# Adafruit_Mini_PiTFT_-_135x240_Color_TFT.net
KiCad netlist of a schematic drawn in EAGLE
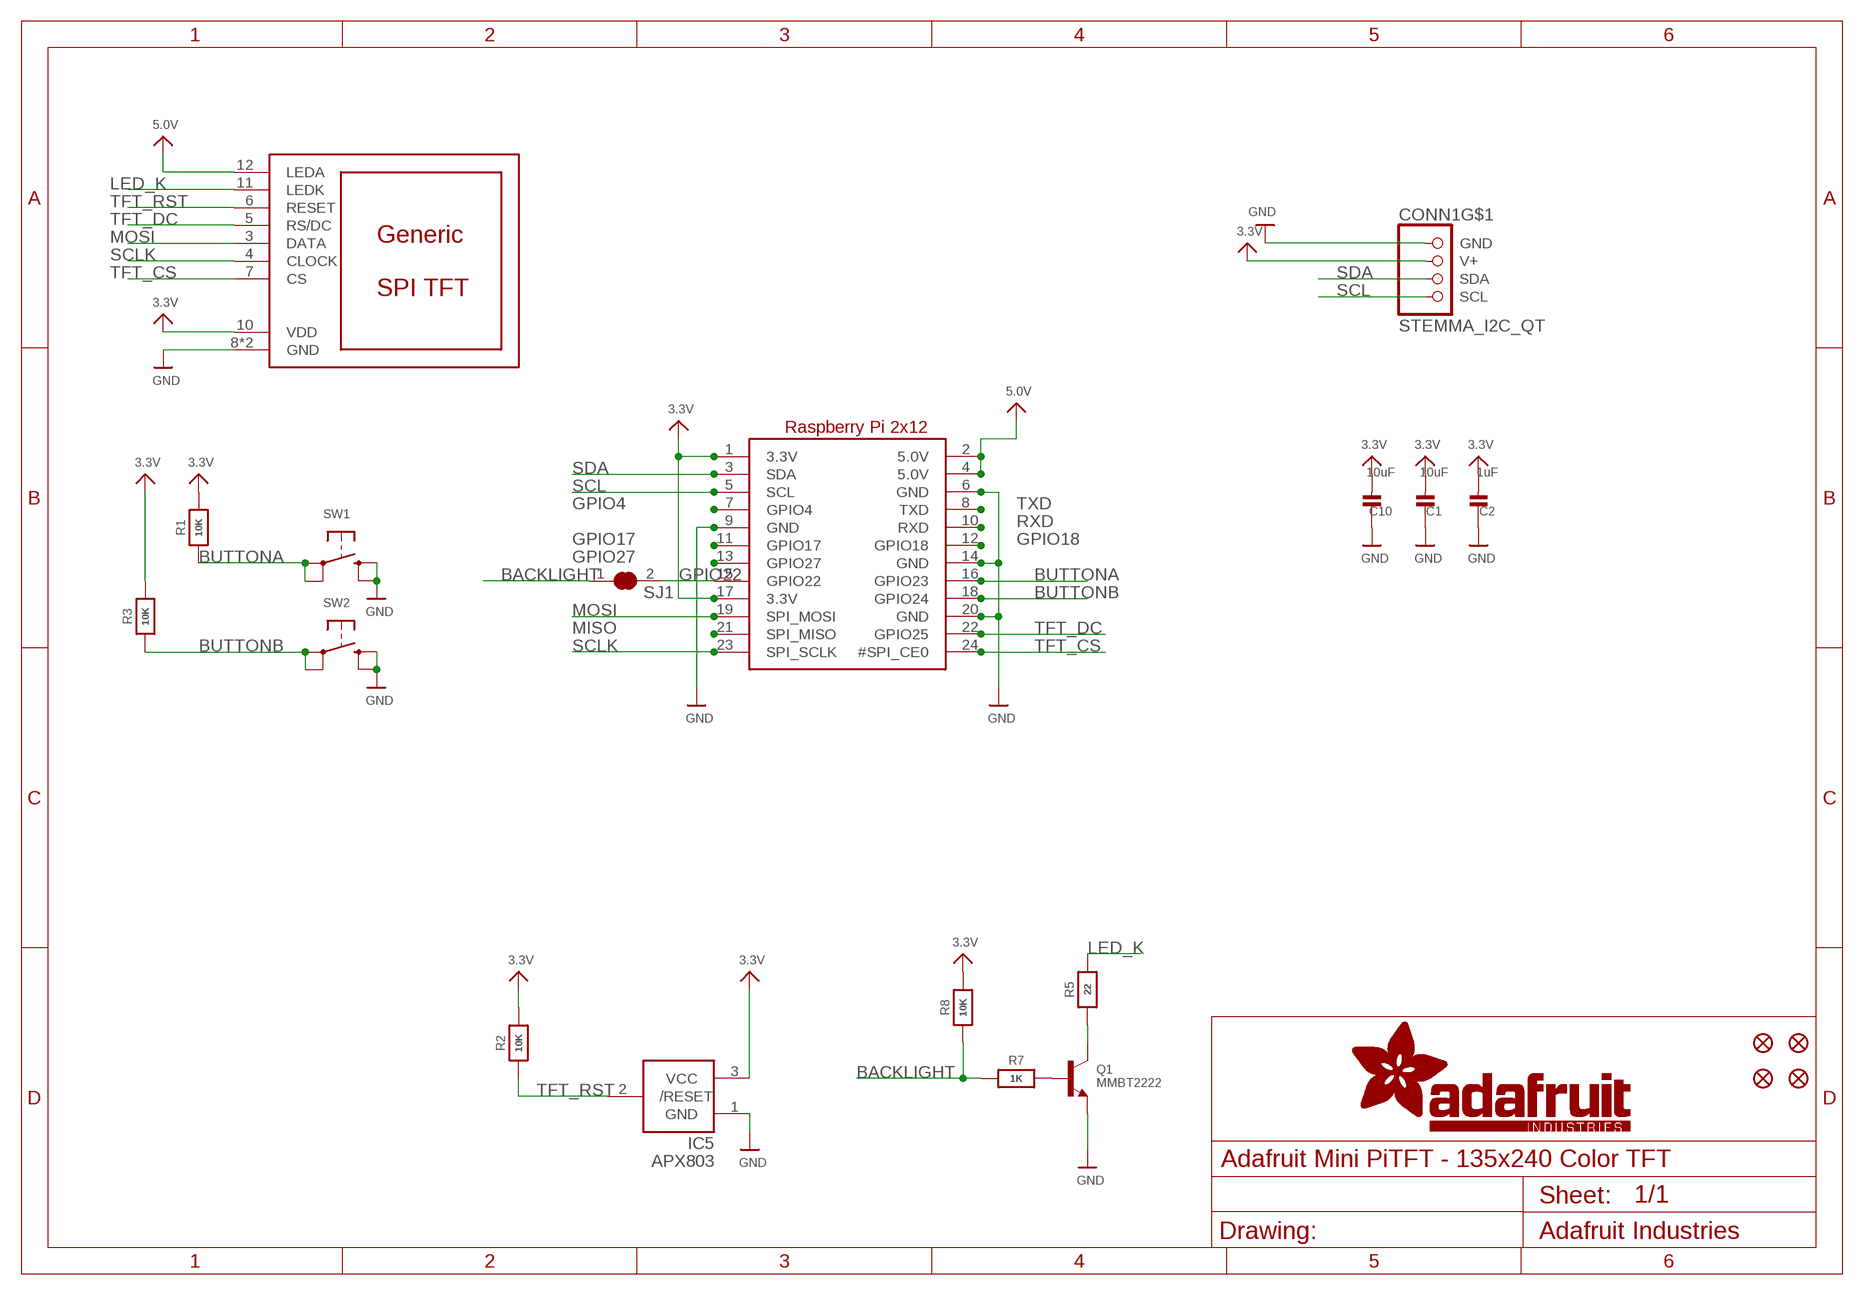
[diagram p0: schematic, sheet 1]

(export (version "E")
  (design (tool "Eeschema 10.0.6"))
  (components
    (comp (ref "C1")
      (value "10uF")
      (footprint "eagle-import:0805-NO")
      (libsource (lib "eagle-import") (part "CAP_CERAMIC0805-NOOUTLINE"))
    )
    (comp (ref "C2")
      (value "1uF")
      (footprint "eagle-import:0603-NO")
      (libsource (lib "eagle-import") (part "CAP_CERAMIC0603_NO"))
    )
    (comp (ref "C10")
      (value "10uF")
      (footprint "eagle-import:0805-NO")
      (libsource (lib "eagle-import") (part "CAP_CERAMIC0805-NOOUTLINE"))
    )
    (comp (ref "CONN1")
      (value "STEMMA_I2C_QT")
      (footprint "eagle-import:JST_SH4")
      (libsource (lib "eagle-import") (part "STEMMA_I2C_QT"))
    )
    (comp (ref "DISP1")
      (value "DISP_LCD_GENERIC_SPI_1.14IN_13P")
      (footprint "eagle-import:TFT_1.14IN_240X135_WRAPAROUND")
      (libsource (lib "eagle-import") (part "DISP_LCD_GENERIC_SPI_1.14IN_13P"))
    )
    (comp (ref "FID1")
      (value "FIDUCIAL_1MM")
      (footprint "eagle-import:FIDUCIAL_1MM")
      (libsource (lib "eagle-import") (part "FIDUCIAL_1MM"))
    )
    (comp (ref "FID2")
      (value "FIDUCIAL_1MM")
      (footprint "eagle-import:FIDUCIAL_1MM")
      (libsource (lib "eagle-import") (part "FIDUCIAL_1MM"))
    )
    (comp (ref "FID3")
      (value "FIDUCIAL_1MM")
      (footprint "eagle-import:FIDUCIAL_1MM")
      (libsource (lib "eagle-import") (part "FIDUCIAL_1MM"))
    )
    (comp (ref "FID4")
      (value "FIDUCIAL_1MM")
      (footprint "eagle-import:FIDUCIAL_1MM")
      (libsource (lib "eagle-import") (part "FIDUCIAL_1MM"))
    )
    (comp (ref "IC5")
      (value "APX803")
      (footprint "eagle-import:SOT23")
      (libsource (lib "eagle-import") (part "AXP083-SAG"))
    )
    (comp (ref "Q1")
      (value "MMBT2222")
      (footprint "eagle-import:SOT23-WIDE")
      (libsource (lib "eagle-import") (part "TRANSISTOR_NPNWIDE"))
    )
    (comp (ref "R1")
      (value "10K")
      (footprint "eagle-import:0603-NO")
      (libsource (lib "eagle-import") (part "RESISTOR_0603_NOOUT"))
    )
    (comp (ref "R2")
      (value "10K")
      (footprint "eagle-import:0603-NO")
      (libsource (lib "eagle-import") (part "RESISTOR_0603_NOOUT"))
    )
    (comp (ref "R3")
      (value "10K")
      (footprint "eagle-import:0603-NO")
      (libsource (lib "eagle-import") (part "RESISTOR_0603_NOOUT"))
    )
    (comp (ref "R5")
      (value "22")
      (footprint "eagle-import:0603-NO")
      (libsource (lib "eagle-import") (part "RESISTOR_0603_NOOUT"))
    )
    (comp (ref "R7")
      (value "1K")
      (footprint "eagle-import:0603-NO")
      (libsource (lib "eagle-import") (part "RESISTOR_0603_NOOUT"))
    )
    (comp (ref "R8")
      (value "10K")
      (footprint "eagle-import:0603-NO")
      (libsource (lib "eagle-import") (part "RESISTOR_0603_NOOUT"))
    )
    (comp (ref "RASPI1")
      (value "RASPBERRYPI_2X12_THMSMT")
      (footprint "eagle-import:RASPBERRYPI_2X12_THMSMT")
      (libsource (lib "eagle-import") (part "RASPBERRYPI_2X12_THMSMT"))
    )
    (comp (ref "SJ1")
      (value "SOLDERJUMPER_CLOSED")
      (footprint "eagle-import:SOLDERJUMPER_CLOSEDWIRE")
      (libsource (lib "eagle-import") (part "SOLDERJUMPER_CLOSED"))
    )
    (comp (ref "SW1")
      (value "SWITCH_TACT_SMT_EVQQ2_SMALL")
      (footprint "eagle-import:EVQ-Q2_SMALLER")
      (libsource (lib "eagle-import") (part "SWITCH_TACT_SMT_EVQQ2_SMALL"))
    )
    (comp (ref "SW2")
      (value "SWITCH_TACT_SMT_EVQQ2_SMALL")
      (footprint "eagle-import:EVQ-Q2_SMALLER")
      (libsource (lib "eagle-import") (part "SWITCH_TACT_SMT_EVQQ2_SMALL"))
    )
  )
  (nets
    (net (code "1") (name "/BACKLIGHT") (class "Default")
      (node (ref "R7") (pin "1") (pinfunction "1_1") (pintype "passive"))
      (node (ref "R8") (pin "1") (pinfunction "1_1") (pintype "passive"))
      (node (ref "SJ1") (pin "1") (pinfunction "1_1") (pintype "passive"))
    )
    (net (code "2") (name "/BUTTONA") (class "Default")
      (node (ref "R1") (pin "1") (pinfunction "1_1") (pintype "passive"))
      (node (ref "RASPI1") (pin "16") (pinfunction "GPIO23_16") (pintype "bidirectional"))
      (node (ref "SW1") (pin "A") (pinfunction "P_A") (pintype "passive"))
      (node (ref "SW1") (pin "A'") (pinfunction "P1_A'") (pintype "passive"))
    )
    (net (code "3") (name "/BUTTONB") (class "Default")
      (node (ref "R3") (pin "1") (pinfunction "1_1") (pintype "passive"))
      (node (ref "RASPI1") (pin "18") (pinfunction "GPIO24_18") (pintype "bidirectional"))
      (node (ref "SW2") (pin "A") (pinfunction "P_A") (pintype "passive"))
      (node (ref "SW2") (pin "A'") (pinfunction "P1_A'") (pintype "passive"))
    )
    (net (code "4") (name "/GPIO4") (class "Default")
      (node (ref "RASPI1") (pin "7") (pinfunction "GPIO4_7") (pintype "bidirectional"))
    )
    (net (code "5") (name "/GPIO17") (class "Default")
      (node (ref "RASPI1") (pin "11") (pinfunction "GPIO17_11") (pintype "bidirectional"))
    )
    (net (code "6") (name "/GPIO18") (class "Default")
      (node (ref "RASPI1") (pin "12") (pinfunction "GPIO18_12") (pintype "bidirectional"))
    )
    (net (code "7") (name "/GPIO22") (class "Default")
      (node (ref "RASPI1") (pin "15") (pinfunction "GPIO22_15") (pintype "bidirectional"))
      (node (ref "SJ1") (pin "2") (pinfunction "2_2") (pintype "passive"))
    )
    (net (code "8") (name "/GPIO27") (class "Default")
      (node (ref "RASPI1") (pin "13") (pinfunction "GPIO27_13") (pintype "bidirectional"))
    )
    (net (code "9") (name "/LED_K") (class "Default")
      (node (ref "DISP1") (pin "11") (pinfunction "LEDK_11") (pintype "input"))
      (node (ref "R5") (pin "2") (pinfunction "2_2") (pintype "passive"))
    )
    (net (code "10") (name "/MISO") (class "Default")
      (node (ref "RASPI1") (pin "21") (pinfunction "SPI_MISO_21") (pintype "bidirectional"))
    )
    (net (code "11") (name "/MOSI") (class "Default")
      (node (ref "DISP1") (pin "3") (pinfunction "DATA_3") (pintype "bidirectional"))
      (node (ref "RASPI1") (pin "19") (pinfunction "SPI_MOSI_19") (pintype "bidirectional"))
    )
    (net (code "12") (name "/RXD") (class "Default")
      (node (ref "RASPI1") (pin "10") (pinfunction "RXD_10") (pintype "bidirectional"))
    )
    (net (code "13") (name "/SCL") (class "Default")
      (node (ref "CONN1") (pin "4") (pinfunction "SCL_4") (pintype "passive"))
      (node (ref "RASPI1") (pin "5") (pinfunction "SCL_5") (pintype "bidirectional"))
    )
    (net (code "14") (name "/SCLK") (class "Default")
      (node (ref "DISP1") (pin "4") (pinfunction "CLOCK_4") (pintype "input"))
      (node (ref "RASPI1") (pin "23") (pinfunction "SPI_SCLK_23") (pintype "bidirectional"))
    )
    (net (code "15") (name "/SDA") (class "Default")
      (node (ref "CONN1") (pin "3") (pinfunction "SDA_3") (pintype "passive"))
      (node (ref "RASPI1") (pin "3") (pinfunction "SDA_3") (pintype "bidirectional"))
    )
    (net (code "16") (name "/TFT_CS") (class "Default")
      (node (ref "DISP1") (pin "7") (pinfunction "CS_7") (pintype "input"))
      (node (ref "RASPI1") (pin "24") (pinfunction "#SPI_CE0_24") (pintype "bidirectional"))
    )
    (net (code "17") (name "/TFT_DC") (class "Default")
      (node (ref "DISP1") (pin "5") (pinfunction "RS/DC_5") (pintype "input"))
      (node (ref "RASPI1") (pin "22") (pinfunction "GPIO25_22") (pintype "bidirectional"))
    )
    (net (code "18") (name "/TFT_RST") (class "Default")
      (node (ref "DISP1") (pin "6") (pinfunction "RESET_6") (pintype "input"))
      (node (ref "IC5") (pin "2") (pinfunction "/RESET_2") (pintype "output"))
      (node (ref "R2") (pin "1") (pinfunction "1_1") (pintype "passive"))
    )
    (net (code "19") (name "/TXD") (class "Default")
      (node (ref "RASPI1") (pin "8") (pinfunction "TXD_8") (pintype "bidirectional"))
    )
    (net (code "20") (name "3.3V") (class "Default")
      (node (ref "C1") (pin "2") (pinfunction "2_2") (pintype "passive"))
      (node (ref "C10") (pin "2") (pinfunction "2_2") (pintype "passive"))
      (node (ref "C2") (pin "2") (pinfunction "2_2") (pintype "passive"))
      (node (ref "CONN1") (pin "2") (pinfunction "V+_2") (pintype "passive"))
      (node (ref "DISP1") (pin "10") (pinfunction "VDD_10") (pintype "power_in"))
      (node (ref "IC5") (pin "3") (pinfunction "VCC_3") (pintype "power_in"))
      (node (ref "R1") (pin "2") (pinfunction "2_2") (pintype "passive"))
      (node (ref "R2") (pin "2") (pinfunction "2_2") (pintype "passive"))
      (node (ref "R3") (pin "2") (pinfunction "2_2") (pintype "passive"))
      (node (ref "R8") (pin "2") (pinfunction "2_2") (pintype "passive"))
      (node (ref "RASPI1") (pin "1") (pinfunction "3.3V_1") (pintype "power_in"))
      (node (ref "RASPI1") (pin "17") (pinfunction "3.3V_17") (pintype "power_in"))
    )
    (net (code "21") (name "5.0V") (class "Default")
      (node (ref "DISP1") (pin "12") (pinfunction "LEDA_12") (pintype "input"))
      (node (ref "RASPI1") (pin "2") (pinfunction "5.0V_2") (pintype "power_in"))
      (node (ref "RASPI1") (pin "4") (pinfunction "5.0V_4") (pintype "power_in"))
    )
    (net (code "22") (name "GND") (class "Default")
      (node (ref "C1") (pin "1") (pinfunction "1_1") (pintype "passive"))
      (node (ref "C10") (pin "1") (pinfunction "1_1") (pintype "passive"))
      (node (ref "C2") (pin "1") (pinfunction "1_1") (pintype "passive"))
      (node (ref "CONN1") (pin "1") (pinfunction "GND_1") (pintype "passive"))
      (node (ref "DISP1") (pin "13") (pinfunction "GND_13") (pintype "power_in"))
      (node (ref "DISP1") (pin "8") (pinfunction "GND_8") (pintype "power_in"))
      (node (ref "IC5") (pin "1") (pinfunction "GND_1") (pintype "power_in"))
      (node (ref "Q1") (pin "2") (pinfunction "E_2") (pintype "passive"))
      (node (ref "RASPI1") (pin "14") (pinfunction "GND_14") (pintype "power_in"))
      (node (ref "RASPI1") (pin "20") (pinfunction "GND_20") (pintype "power_in"))
      (node (ref "RASPI1") (pin "6") (pinfunction "GND_6") (pintype "power_in"))
      (node (ref "RASPI1") (pin "9") (pinfunction "GND_9") (pintype "power_in"))
      (node (ref "SW1") (pin "B") (pinfunction "S_B") (pintype "passive"))
      (node (ref "SW1") (pin "B'") (pinfunction "S1_B'") (pintype "passive"))
      (node (ref "SW2") (pin "B") (pinfunction "S_B") (pintype "passive"))
      (node (ref "SW2") (pin "B'") (pinfunction "S1_B'") (pintype "passive"))
    )
    (net (code "23") (name "Net-(Q1-B)") (class "Default")
      (node (ref "Q1") (pin "1") (pinfunction "B_1") (pintype "passive"))
      (node (ref "R7") (pin "2") (pinfunction "2_2") (pintype "passive"))
    )
    (net (code "24") (name "Net-(Q1-C)") (class "Default")
      (node (ref "Q1") (pin "3") (pinfunction "C_3") (pintype "passive"))
      (node (ref "R5") (pin "1") (pinfunction "1_1") (pintype "passive"))
    )
  )
)
